# me433_pic32_pcb.net
KiCad netlist of a schematic drawn in EAGLE
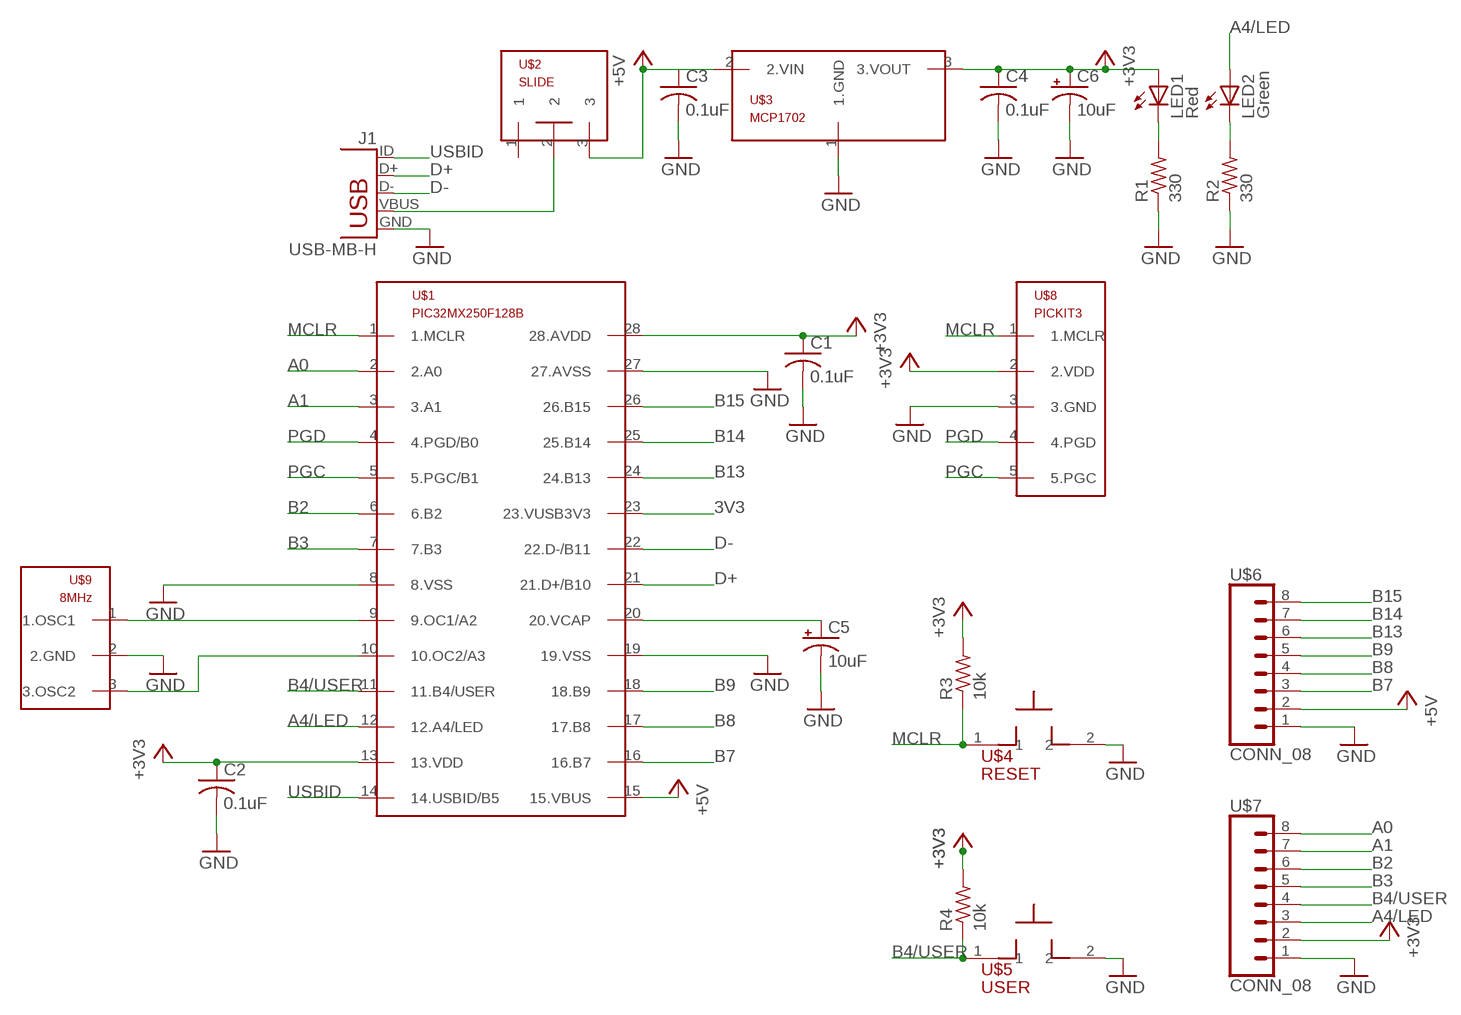
[diagram p0: schematic, sheet 1]

(export (version "E")
  (design (tool "Eeschema 10.0.6"))
  (components
    (comp (ref "C1")
      (value "0.1uF")
      (footprint "eagle-import:C025-025X050")
      (libsource (lib "eagle-import") (part "C-US025-025X050"))
    )
    (comp (ref "C2")
      (value "0.1uF")
      (footprint "eagle-import:C025-025X050")
      (libsource (lib "eagle-import") (part "C-US025-025X050"))
    )
    (comp (ref "C3")
      (value "0.1uF")
      (footprint "eagle-import:C025-025X050")
      (libsource (lib "eagle-import") (part "C-US025-025X050"))
    )
    (comp (ref "C4")
      (value "0.1uF")
      (footprint "eagle-import:C025-025X050")
      (libsource (lib "eagle-import") (part "C-US025-025X050"))
    )
    (comp (ref "C5")
      (value "10uF")
      (footprint "eagle-import:B45181B")
      (libsource (lib "eagle-import") (part "CPOL-USB45181B"))
    )
    (comp (ref "C6")
      (value "10uF")
      (footprint "eagle-import:B45181B")
      (libsource (lib "eagle-import") (part "CPOL-USB45181B"))
    )
    (comp (ref "J1")
      (value "USB-MB-H")
      (footprint "eagle-import:USB-MB-H")
      (libsource (lib "eagle-import") (part "USB-MB-H"))
    )
    (comp (ref "LED1")
      (value "Red")
      (footprint "eagle-import:LED3MM")
      (libsource (lib "eagle-import") (part "LED3MM"))
    )
    (comp (ref "LED2")
      (value "Green")
      (footprint "eagle-import:LED3MM")
      (libsource (lib "eagle-import") (part "LED3MM"))
    )
    (comp (ref "R1")
      (value "330")
      (footprint "eagle-import:0207_10")
      (libsource (lib "eagle-import") (part "R-US_0207/10"))
    )
    (comp (ref "R2")
      (value "330")
      (footprint "eagle-import:0207_10")
      (libsource (lib "eagle-import") (part "R-US_0207/10"))
    )
    (comp (ref "R3")
      (value "10k")
      (footprint "eagle-import:0207_10")
      (libsource (lib "eagle-import") (part "R-US_0207/10"))
    )
    (comp (ref "R4")
      (value "10k")
      (footprint "eagle-import:0207_10")
      (libsource (lib "eagle-import") (part "R-US_0207/10"))
    )
    (comp (ref "U$1")
      (value "PIC32MX250F128B")
      (footprint "eagle-import:DIL28-3")
      (libsource (lib "eagle-import") (part "PIC32MX250F128B"))
    )
    (comp (ref "U$2")
      (value "SLIDE")
      (footprint "eagle-import:SLIDE")
      (libsource (lib "eagle-import") (part "SLIDE"))
    )
    (comp (ref "U$3")
      (value "MCP1702")
      (footprint "eagle-import:TO92")
      (libsource (lib "eagle-import") (part "MCP1702"))
    )
    (comp (ref "U$4")
      (value "RESET")
      (footprint "eagle-import:PB")
      (libsource (lib "eagle-import") (part "PB"))
    )
    (comp (ref "U$5")
      (value "USER")
      (footprint "eagle-import:PB")
      (libsource (lib "eagle-import") (part "PB"))
    )
    (comp (ref "U$6")
      (value "CONN_08")
      (footprint "eagle-import:1X08")
      (libsource (lib "eagle-import") (part "CONN_08"))
    )
    (comp (ref "U$7")
      (value "CONN_08")
      (footprint "eagle-import:1X08")
      (libsource (lib "eagle-import") (part "CONN_08"))
    )
    (comp (ref "U$8")
      (value "PICKIT3")
      (footprint "eagle-import:1X05")
      (libsource (lib "eagle-import") (part "PICKIT3"))
    )
    (comp (ref "U$9")
      (value "8MHz")
      (footprint "eagle-import:OSC")
      (libsource (lib "eagle-import") (part "OSC"))
    )
  )
  (nets
    (net (code "1") (name "+3V3") (class "Default")
      (node (ref "C1") (pin "1") (pinfunction "1_1") (pintype "passive"))
      (node (ref "C2") (pin "1") (pinfunction "1_1") (pintype "passive"))
      (node (ref "C4") (pin "1") (pinfunction "1_1") (pintype "passive"))
      (node (ref "C6") (pin "+") (pinfunction "+_+") (pintype "passive"))
      (node (ref "LED1") (pin "A") (pinfunction "A_A") (pintype "passive"))
      (node (ref "R3") (pin "2") (pinfunction "2_2") (pintype "passive"))
      (node (ref "R4") (pin "2") (pinfunction "2_2") (pintype "passive"))
      (node (ref "U$1") (pin "13") (pinfunction "13.VDD_13") (pintype "bidirectional"))
      (node (ref "U$1") (pin "28") (pinfunction "28.AVDD_28") (pintype "bidirectional"))
      (node (ref "U$3") (pin "3") (pinfunction "3.VOUT_3") (pintype "bidirectional"))
      (node (ref "U$7") (pin "2") (pinfunction "2_2") (pintype "passive"))
      (node (ref "U$8") (pin "2") (pinfunction "2.VDD_2") (pintype "bidirectional"))
    )
    (net (code "2") (name "+5V") (class "Default")
      (node (ref "U$1") (pin "15") (pinfunction "15.VBUS_15") (pintype "bidirectional"))
      (node (ref "U$2") (pin "3") (pinfunction "3_3") (pintype "bidirectional"))
      (node (ref "U$3") (pin "2") (pinfunction "2.VIN_2") (pintype "bidirectional"))
      (node (ref "U$6") (pin "2") (pinfunction "2_2") (pintype "passive"))
    )
    (net (code "3") (name "/3V3") (class "Default")
      (node (ref "U$1") (pin "23") (pinfunction "23.VUSB3V3_23") (pintype "bidirectional"))
    )
    (net (code "4") (name "/A0") (class "Default")
      (node (ref "U$1") (pin "2") (pinfunction "2.A0_2") (pintype "bidirectional"))
      (node (ref "U$7") (pin "8") (pinfunction "8_8") (pintype "passive"))
    )
    (net (code "5") (name "/A1") (class "Default")
      (node (ref "U$1") (pin "3") (pinfunction "3.A1_3") (pintype "bidirectional"))
      (node (ref "U$7") (pin "7") (pinfunction "7_7") (pintype "passive"))
    )
    (net (code "6") (name "/A4{slash}LED") (class "Default")
      (node (ref "LED2") (pin "A") (pinfunction "A_A") (pintype "passive"))
      (node (ref "U$1") (pin "12") (pinfunction "12.A4/LED_12") (pintype "bidirectional"))
      (node (ref "U$7") (pin "3") (pinfunction "3_3") (pintype "passive"))
    )
    (net (code "7") (name "/B2") (class "Default")
      (node (ref "U$1") (pin "6") (pinfunction "6.B2_6") (pintype "bidirectional"))
      (node (ref "U$7") (pin "6") (pinfunction "6_6") (pintype "passive"))
    )
    (net (code "8") (name "/B3") (class "Default")
      (node (ref "U$1") (pin "7") (pinfunction "7.B3_7") (pintype "bidirectional"))
      (node (ref "U$7") (pin "5") (pinfunction "5_5") (pintype "passive"))
    )
    (net (code "9") (name "/B4{slash}USER") (class "Default")
      (node (ref "R4") (pin "1") (pinfunction "1_1") (pintype "passive"))
      (node (ref "U$1") (pin "11") (pinfunction "11.B4/USER_11") (pintype "bidirectional"))
      (node (ref "U$5") (pin "1") (pinfunction "1_1") (pintype "bidirectional"))
      (node (ref "U$7") (pin "4") (pinfunction "4_4") (pintype "passive"))
    )
    (net (code "10") (name "/B7") (class "Default")
      (node (ref "U$1") (pin "16") (pinfunction "16.B7_16") (pintype "bidirectional"))
      (node (ref "U$6") (pin "3") (pinfunction "3_3") (pintype "passive"))
    )
    (net (code "11") (name "/B8") (class "Default")
      (node (ref "U$1") (pin "17") (pinfunction "17.B8_17") (pintype "bidirectional"))
      (node (ref "U$6") (pin "4") (pinfunction "4_4") (pintype "passive"))
    )
    (net (code "12") (name "/B9") (class "Default")
      (node (ref "U$1") (pin "18") (pinfunction "18.B9_18") (pintype "bidirectional"))
      (node (ref "U$6") (pin "5") (pinfunction "5_5") (pintype "passive"))
    )
    (net (code "13") (name "/B13") (class "Default")
      (node (ref "U$1") (pin "24") (pinfunction "24.B13_24") (pintype "bidirectional"))
      (node (ref "U$6") (pin "6") (pinfunction "6_6") (pintype "passive"))
    )
    (net (code "14") (name "/B14") (class "Default")
      (node (ref "U$1") (pin "25") (pinfunction "25.B14_25") (pintype "bidirectional"))
      (node (ref "U$6") (pin "7") (pinfunction "7_7") (pintype "passive"))
    )
    (net (code "15") (name "/B15") (class "Default")
      (node (ref "U$1") (pin "26") (pinfunction "26.B15_26") (pintype "bidirectional"))
      (node (ref "U$6") (pin "8") (pinfunction "8_8") (pintype "passive"))
    )
    (net (code "16") (name "/D+") (class "Default")
      (node (ref "J1") (pin "D+") (pinfunction "D+_D+") (pintype "bidirectional"))
      (node (ref "U$1") (pin "21") (pinfunction "21.D+/B10_21") (pintype "bidirectional"))
    )
    (net (code "17") (name "/D-") (class "Default")
      (node (ref "J1") (pin "D-") (pinfunction "D-_D-") (pintype "bidirectional"))
      (node (ref "U$1") (pin "22") (pinfunction "22.D-/B11_22") (pintype "bidirectional"))
    )
    (net (code "18") (name "/MCLR") (class "Default")
      (node (ref "R3") (pin "1") (pinfunction "1_1") (pintype "passive"))
      (node (ref "U$1") (pin "1") (pinfunction "1.MCLR_1") (pintype "bidirectional"))
      (node (ref "U$4") (pin "1") (pinfunction "1_1") (pintype "bidirectional"))
      (node (ref "U$8") (pin "1") (pinfunction "1.MCLR_1") (pintype "bidirectional"))
    )
    (net (code "19") (name "/PGC") (class "Default")
      (node (ref "U$1") (pin "5") (pinfunction "5.PGC/B1_5") (pintype "bidirectional"))
      (node (ref "U$8") (pin "5") (pinfunction "5.PGC_5") (pintype "bidirectional"))
    )
    (net (code "20") (name "/PGD") (class "Default")
      (node (ref "U$1") (pin "4") (pinfunction "4.PGD/B0_4") (pintype "bidirectional"))
      (node (ref "U$8") (pin "4") (pinfunction "4.PGD_4") (pintype "bidirectional"))
    )
    (net (code "21") (name "/USBID") (class "Default")
      (node (ref "J1") (pin "ID") (pinfunction "ID_ID") (pintype "bidirectional"))
      (node (ref "U$1") (pin "14") (pinfunction "14.USBID/B5_14") (pintype "bidirectional"))
    )
    (net (code "22") (name "GND") (class "Default")
      (node (ref "C1") (pin "2") (pinfunction "2_2") (pintype "passive"))
      (node (ref "C2") (pin "2") (pinfunction "2_2") (pintype "passive"))
      (node (ref "C3") (pin "2") (pinfunction "2_2") (pintype "passive"))
      (node (ref "C4") (pin "2") (pinfunction "2_2") (pintype "passive"))
      (node (ref "C5") (pin "-") (pinfunction "-_-") (pintype "passive"))
      (node (ref "C6") (pin "-") (pinfunction "-_-") (pintype "passive"))
      (node (ref "J1") (pin "GND") (pinfunction "GND_GND") (pintype "bidirectional"))
      (node (ref "R1") (pin "1") (pinfunction "1_1") (pintype "passive"))
      (node (ref "R2") (pin "1") (pinfunction "1_1") (pintype "passive"))
      (node (ref "U$1") (pin "19") (pinfunction "19.VSS_19") (pintype "bidirectional"))
      (node (ref "U$1") (pin "27") (pinfunction "27.AVSS_27") (pintype "bidirectional"))
      (node (ref "U$1") (pin "8") (pinfunction "8.VSS_8") (pintype "bidirectional"))
      (node (ref "U$3") (pin "1") (pinfunction "1.GND_1") (pintype "bidirectional"))
      (node (ref "U$4") (pin "2") (pinfunction "2_2") (pintype "bidirectional"))
      (node (ref "U$5") (pin "2") (pinfunction "2_2") (pintype "bidirectional"))
      (node (ref "U$6") (pin "1") (pinfunction "1_1") (pintype "passive"))
      (node (ref "U$7") (pin "1") (pinfunction "1_1") (pintype "passive"))
      (node (ref "U$8") (pin "3") (pinfunction "3.GND_3") (pintype "bidirectional"))
      (node (ref "U$9") (pin "2") (pinfunction "2.GND_2") (pintype "bidirectional"))
    )
    (net (code "23") (name "Net-(J1-PadVBUS)") (class "Default")
      (node (ref "J1") (pin "VBUS") (pinfunction "VBUS_VBUS") (pintype "bidirectional"))
      (node (ref "U$2") (pin "2") (pinfunction "2_2") (pintype "bidirectional"))
    )
    (net (code "24") (name "Net-(LED1-C)") (class "Default")
      (node (ref "LED1") (pin "K") (pinfunction "C_K") (pintype "passive"))
      (node (ref "R1") (pin "2") (pinfunction "2_2") (pintype "passive"))
    )
    (net (code "25") (name "Net-(LED2-C)") (class "Default")
      (node (ref "LED2") (pin "K") (pinfunction "C_K") (pintype "passive"))
      (node (ref "R2") (pin "2") (pinfunction "2_2") (pintype "passive"))
    )
    (net (code "26") (name "Net-(U$1-9.OC1{slash}A2)") (class "Default")
      (node (ref "U$1") (pin "9") (pinfunction "9.OC1/A2_9") (pintype "bidirectional"))
      (node (ref "U$9") (pin "1") (pinfunction "1.OSC1_1") (pintype "bidirectional"))
    )
    (net (code "27") (name "Net-(U$1-10.OC2{slash}A3)") (class "Default")
      (node (ref "U$1") (pin "10") (pinfunction "10.OC2/A3_10") (pintype "bidirectional"))
      (node (ref "U$9") (pin "3") (pinfunction "3.OSC2_3") (pintype "bidirectional"))
    )
    (net (code "28") (name "Net-(U$1-20.VCAP)") (class "Default")
      (node (ref "C5") (pin "+") (pinfunction "+_+") (pintype "passive"))
      (node (ref "U$1") (pin "20") (pinfunction "20.VCAP_20") (pintype "bidirectional"))
    )
    (net (code "29") (name "unconnected-(C3-Pad1)") (class "Default")
      (node (ref "C3") (pin "1") (pinfunction "1_1") (pintype "passive"))
    )
    (net (code "30") (name "unconnected-(U$2-Pad1)") (class "Default")
      (node (ref "U$2") (pin "1") (pinfunction "1_1") (pintype "bidirectional"))
    )
  )
)
